# USB.net
KiCad netlist of a schematic drawn in EasyEDA Pro
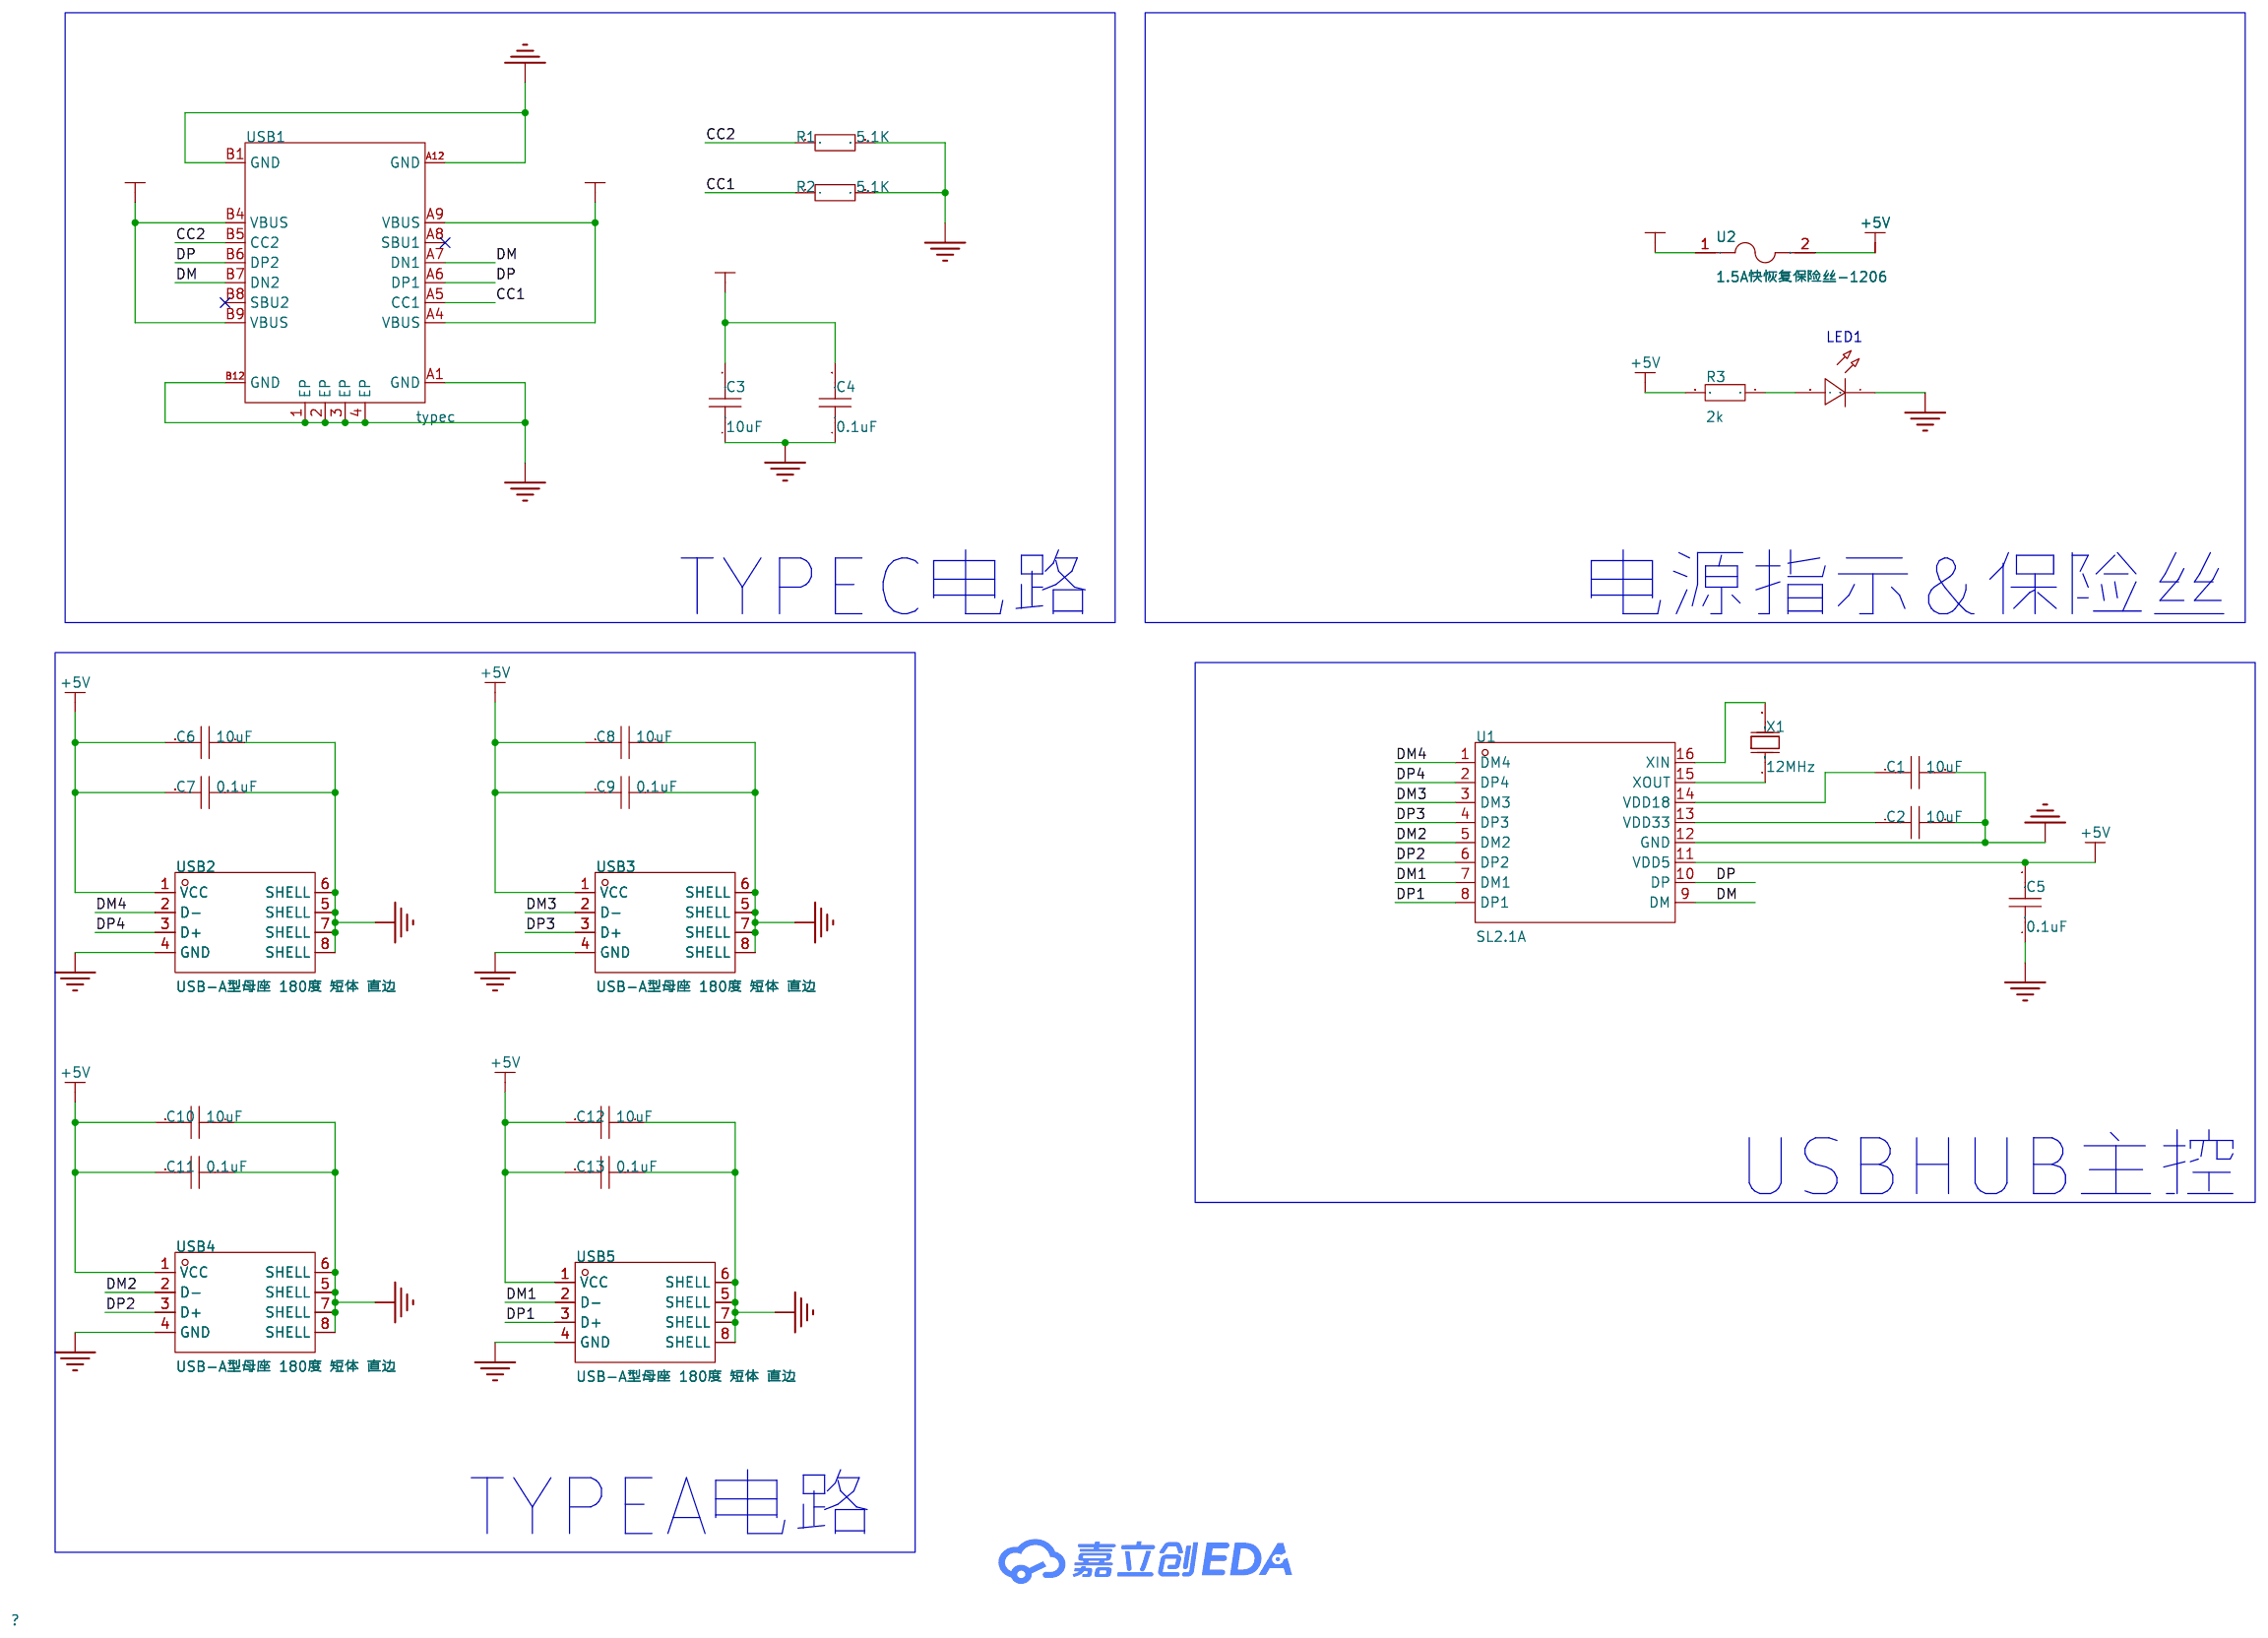
[diagram p0: schematic sheet]

(export (version "E")
  (design (tool "Eeschema 10.0.6"))
  (components
    (comp (ref "C1")
      (value "10uF")
      (footprint "easyedapro:C0805")
      (libsource (lib "easyedapro") (part "CapAcitance"))
    )
    (comp (ref "C2")
      (value "10uF")
      (footprint "easyedapro:C0805")
      (libsource (lib "easyedapro") (part "CapAcitance"))
    )
    (comp (ref "C3")
      (value "10uF")
      (footprint "easyedapro:C0805")
      (libsource (lib "easyedapro") (part "CapAcitance"))
    )
    (comp (ref "C4")
      (value "0.1uF")
      (footprint "easyedapro:C0805")
      (libsource (lib "easyedapro") (part "CapAcitance"))
    )
    (comp (ref "C5")
      (value "0.1uF")
      (footprint "easyedapro:C0805")
      (libsource (lib "easyedapro") (part "CapAcitance"))
    )
    (comp (ref "C6")
      (value "10uF")
      (footprint "easyedapro:C0805")
      (libsource (lib "easyedapro") (part "CapAcitance"))
    )
    (comp (ref "C7")
      (value "0.1uF")
      (footprint "easyedapro:C0805")
      (libsource (lib "easyedapro") (part "CapAcitance"))
    )
    (comp (ref "C8")
      (value "10uF")
      (footprint "easyedapro:C0805")
      (libsource (lib "easyedapro") (part "CapAcitance"))
    )
    (comp (ref "C9")
      (value "0.1uF")
      (footprint "easyedapro:C0805")
      (libsource (lib "easyedapro") (part "CapAcitance"))
    )
    (comp (ref "C10")
      (value "10uF")
      (footprint "easyedapro:C0805")
      (libsource (lib "easyedapro") (part "CapAcitance"))
    )
    (comp (ref "C11")
      (value "0.1uF")
      (footprint "easyedapro:C0805")
      (libsource (lib "easyedapro") (part "CapAcitance"))
    )
    (comp (ref "C12")
      (value "10uF")
      (footprint "easyedapro:C0805")
      (libsource (lib "easyedapro") (part "CapAcitance"))
    )
    (comp (ref "C13")
      (value "0.1uF")
      (footprint "easyedapro:C0805")
      (libsource (lib "easyedapro") (part "CapAcitance"))
    )
    (comp (ref "LED1")
      (value "~")
      (footprint "easyedapro:LED_0805")
      (libsource (lib "easyedapro") (part "LED_G"))
    )
    (comp (ref "R1") (value "5.1K") (footprint "easyedapro:R0805") (libsource (lib "easyedapro") (part "电阻")))
    (comp (ref "R2") (value "5.1K") (footprint "easyedapro:R0805") (libsource (lib "easyedapro") (part "电阻")))
    (comp (ref "R3") (value "2k") (footprint "easyedapro:R0805") (libsource (lib "easyedapro") (part "电阻")))
    (comp (ref "U1")
      (value "SL2.1A")
      (footprint "easyedapro:SOP-16_L10.0-W3.9-P1.27-LS6.0-BL")
      (description "SL2.1A是一颗高集成度,高性能,低功耗的USB2.0集线器主控芯片，支持USB2.0高速(480MHz),全速(12MHz)和低速模式(1.5MHz)，内置12MHz晶体振荡器。")
      (fields (field (name "Manufacturer") "CoreChips(和芯润德)"))
      (libsource (lib "easyedapro") (part "SL2.1A"))
    )
    (comp (ref "U2")
      (value "1.5A快恢复保险丝-1206")
      (footprint "easyedapro:F1206")
      (libsource (lib "easyedapro") (part "1.5A快恢复保险丝-1206"))
    )
    (comp (ref "USB1")
      (value "typec")
      (footprint "easyedapro:USB-C-SMD_KH-TYPE-C-16P")
      (libsource (lib "easyedapro") (part "TYPEC_C9900016956"))
    )
    (comp (ref "USB2")
      (value "USB-A型母座 180度 短体 直边")
      (footprint "easyedapro:USB-A-SMD_WT_C9900004571")
      (libsource (lib "easyedapro") (part "USB-A型母座 180度 短体 直边"))
    )
    (comp (ref "USB3")
      (value "USB-A型母座 180度 短体 直边")
      (footprint "easyedapro:USB-A-SMD_WT_C9900004571")
      (libsource (lib "easyedapro") (part "USB-A型母座 180度 短体 直边"))
    )
    (comp (ref "USB4")
      (value "USB-A型母座 180度 短体 直边")
      (footprint "easyedapro:USB-A-SMD_WT_C9900004571")
      (libsource (lib "easyedapro") (part "USB-A型母座 180度 短体 直边"))
    )
    (comp (ref "USB5")
      (value "USB-A型母座 180度 短体 直边")
      (footprint "easyedapro:USB-A-SMD_WT_C9900004571")
      (libsource (lib "easyedapro") (part "USB-A型母座 180度 短体 直边"))
    )
    (comp (ref "X1")
      (value "12MHz")
      (footprint "easyedapro:HC-49US_L11.0-W4.6-P4.88")
      (description "晶振类型:直插晶振;频率:12MHz;常温频差:±20ppm;外接负载电容:20pF;频率稳定度(全温):±30ppm;")
      (fields (field (name "Manufacturer Part") "49SAC12000202060") (field (name "Manufacturer") "JGHC(晶光华)"))
      (libsource (lib "easyedapro") (part "49SAC12000202060"))
    )
  )
  (nets
    (net (code "1") (name "+5V") (class "Default")
      (node (ref "C10") (pin "2") (pinfunction "2_2") (pintype "input"))
      (node (ref "C11") (pin "2") (pinfunction "2_2") (pintype "input"))
      (node (ref "C12") (pin "2") (pinfunction "2_2") (pintype "input"))
      (node (ref "C13") (pin "2") (pinfunction "2_2") (pintype "input"))
      (node (ref "C5") (pin "2") (pinfunction "2_2") (pintype "input"))
      (node (ref "C6") (pin "2") (pinfunction "2_2") (pintype "input"))
      (node (ref "C7") (pin "2") (pinfunction "2_2") (pintype "input"))
      (node (ref "C8") (pin "2") (pinfunction "2_2") (pintype "input"))
      (node (ref "C9") (pin "2") (pinfunction "2_2") (pintype "input"))
      (node (ref "R3") (pin "2") (pinfunction "2_2") (pintype "input"))
      (node (ref "U1") (pin "11") (pinfunction "VDD5_11") (pintype "unspecified"))
      (node (ref "U2") (pin "2") (pinfunction "2_2") (pintype "unspecified"))
      (node (ref "USB2") (pin "1") (pinfunction "VCC_1") (pintype "unspecified"))
      (node (ref "USB3") (pin "1") (pinfunction "VCC_1") (pintype "unspecified"))
      (node (ref "USB4") (pin "1") (pinfunction "VCC_1") (pintype "unspecified"))
      (node (ref "USB5") (pin "1") (pinfunction "VCC_1") (pintype "unspecified"))
    )
    (net (code "2") (name "/CC1") (class "Default")
      (node (ref "R2") (pin "1") (pinfunction "1_1") (pintype "input"))
      (node (ref "USB1") (pin "A5") (pinfunction "CC1_A5") (pintype "unspecified"))
    )
    (net (code "3") (name "/CC2") (class "Default")
      (node (ref "R1") (pin "1") (pinfunction "1_1") (pintype "input"))
      (node (ref "USB1") (pin "B5") (pinfunction "CC2_B5") (pintype "unspecified"))
    )
    (net (code "4") (name "/DM") (class "Default")
      (node (ref "U1") (pin "9") (pinfunction "DM_9") (pintype "unspecified"))
      (node (ref "USB1") (pin "A7") (pinfunction "DN1_A7") (pintype "unspecified"))
      (node (ref "USB1") (pin "B7") (pinfunction "DN2_B7") (pintype "unspecified"))
    )
    (net (code "5") (name "/DM1") (class "Default")
      (node (ref "U1") (pin "7") (pinfunction "DM1_7") (pintype "unspecified"))
      (node (ref "USB5") (pin "2") (pinfunction "D-_2") (pintype "unspecified"))
    )
    (net (code "6") (name "/DM2") (class "Default")
      (node (ref "U1") (pin "5") (pinfunction "DM2_5") (pintype "unspecified"))
      (node (ref "USB4") (pin "2") (pinfunction "D-_2") (pintype "unspecified"))
    )
    (net (code "7") (name "/DM3") (class "Default")
      (node (ref "U1") (pin "3") (pinfunction "DM3_3") (pintype "unspecified"))
      (node (ref "USB3") (pin "2") (pinfunction "D-_2") (pintype "unspecified"))
    )
    (net (code "8") (name "/DM4") (class "Default")
      (node (ref "U1") (pin "1") (pinfunction "DM4_1") (pintype "unspecified"))
      (node (ref "USB2") (pin "2") (pinfunction "D-_2") (pintype "unspecified"))
    )
    (net (code "9") (name "/DP") (class "Default")
      (node (ref "U1") (pin "10") (pinfunction "DP_10") (pintype "unspecified"))
      (node (ref "USB1") (pin "A6") (pinfunction "DP1_A6") (pintype "unspecified"))
      (node (ref "USB1") (pin "B6") (pinfunction "DP2_B6") (pintype "unspecified"))
    )
    (net (code "10") (name "/DP1") (class "Default")
      (node (ref "U1") (pin "8") (pinfunction "DP1_8") (pintype "unspecified"))
      (node (ref "USB5") (pin "3") (pinfunction "D+_3") (pintype "unspecified"))
    )
    (net (code "11") (name "/DP2") (class "Default")
      (node (ref "U1") (pin "6") (pinfunction "DP2_6") (pintype "unspecified"))
      (node (ref "USB4") (pin "3") (pinfunction "D+_3") (pintype "unspecified"))
    )
    (net (code "12") (name "/DP3") (class "Default")
      (node (ref "U1") (pin "4") (pinfunction "DP3_4") (pintype "unspecified"))
      (node (ref "USB3") (pin "3") (pinfunction "D+_3") (pintype "unspecified"))
    )
    (net (code "13") (name "/DP4") (class "Default")
      (node (ref "U1") (pin "2") (pinfunction "DP4_2") (pintype "unspecified"))
      (node (ref "USB2") (pin "3") (pinfunction "D+_3") (pintype "unspecified"))
    )
    (net (code "14") (name "GND") (class "Default")
      (node (ref "C1") (pin "2") (pinfunction "2_2") (pintype "input"))
      (node (ref "C10") (pin "1") (pinfunction "1_1") (pintype "input"))
      (node (ref "C11") (pin "1") (pinfunction "1_1") (pintype "input"))
      (node (ref "C12") (pin "1") (pinfunction "1_1") (pintype "input"))
      (node (ref "C13") (pin "1") (pinfunction "1_1") (pintype "input"))
      (node (ref "C2") (pin "2") (pinfunction "2_2") (pintype "input"))
      (node (ref "C3") (pin "1") (pinfunction "1_1") (pintype "input"))
      (node (ref "C4") (pin "1") (pinfunction "1_1") (pintype "input"))
      (node (ref "C5") (pin "1") (pinfunction "1_1") (pintype "input"))
      (node (ref "C6") (pin "1") (pinfunction "1_1") (pintype "input"))
      (node (ref "C7") (pin "1") (pinfunction "1_1") (pintype "input"))
      (node (ref "C8") (pin "1") (pinfunction "1_1") (pintype "input"))
      (node (ref "C9") (pin "1") (pinfunction "1_1") (pintype "input"))
      (node (ref "LED1") (pin "1") (pinfunction "C_1") (pintype "input"))
      (node (ref "R1") (pin "2") (pinfunction "2_2") (pintype "input"))
      (node (ref "R2") (pin "2") (pinfunction "2_2") (pintype "input"))
      (node (ref "U1") (pin "12") (pinfunction "GND_12") (pintype "unspecified"))
      (node (ref "USB1") (pin "1") (pinfunction "EP_1") (pintype "unspecified"))
      (node (ref "USB1") (pin "2") (pinfunction "EP_2") (pintype "unspecified"))
      (node (ref "USB1") (pin "3") (pinfunction "EP_3") (pintype "unspecified"))
      (node (ref "USB1") (pin "4") (pinfunction "EP_4") (pintype "unspecified"))
      (node (ref "USB1") (pin "A1") (pinfunction "GND_A1") (pintype "unspecified"))
      (node (ref "USB1") (pin "A12") (pinfunction "GND_A12") (pintype "unspecified"))
      (node (ref "USB1") (pin "B1") (pinfunction "GND_B1") (pintype "unspecified"))
      (node (ref "USB1") (pin "B12") (pinfunction "GND_B12") (pintype "unspecified"))
      (node (ref "USB2") (pin "4") (pinfunction "GND_4") (pintype "unspecified"))
      (node (ref "USB2") (pin "5") (pinfunction "SHELL_5") (pintype "unspecified"))
      (node (ref "USB2") (pin "6") (pinfunction "SHELL_6") (pintype "unspecified"))
      (node (ref "USB2") (pin "7") (pinfunction "SHELL_7") (pintype "unspecified"))
      (node (ref "USB2") (pin "8") (pinfunction "SHELL_8") (pintype "unspecified"))
      (node (ref "USB3") (pin "4") (pinfunction "GND_4") (pintype "unspecified"))
      (node (ref "USB3") (pin "5") (pinfunction "SHELL_5") (pintype "unspecified"))
      (node (ref "USB3") (pin "6") (pinfunction "SHELL_6") (pintype "unspecified"))
      (node (ref "USB3") (pin "7") (pinfunction "SHELL_7") (pintype "unspecified"))
      (node (ref "USB3") (pin "8") (pinfunction "SHELL_8") (pintype "unspecified"))
      (node (ref "USB4") (pin "4") (pinfunction "GND_4") (pintype "unspecified"))
      (node (ref "USB4") (pin "5") (pinfunction "SHELL_5") (pintype "unspecified"))
      (node (ref "USB4") (pin "6") (pinfunction "SHELL_6") (pintype "unspecified"))
      (node (ref "USB4") (pin "7") (pinfunction "SHELL_7") (pintype "unspecified"))
      (node (ref "USB4") (pin "8") (pinfunction "SHELL_8") (pintype "unspecified"))
      (node (ref "USB5") (pin "4") (pinfunction "GND_4") (pintype "unspecified"))
      (node (ref "USB5") (pin "5") (pinfunction "SHELL_5") (pintype "unspecified"))
      (node (ref "USB5") (pin "6") (pinfunction "SHELL_6") (pintype "unspecified"))
      (node (ref "USB5") (pin "7") (pinfunction "SHELL_7") (pintype "unspecified"))
      (node (ref "USB5") (pin "8") (pinfunction "SHELL_8") (pintype "unspecified"))
    )
    (net (code "15") (name "Net-(LED1-A)") (class "Default")
      (node (ref "LED1") (pin "2") (pinfunction "A_2") (pintype "input"))
      (node (ref "R3") (pin "1") (pinfunction "1_1") (pintype "input"))
    )
    (net (code "16") (name "Net-(U1-VDD18)") (class "Default")
      (node (ref "C1") (pin "1") (pinfunction "1_1") (pintype "input"))
      (node (ref "U1") (pin "14") (pinfunction "VDD18_14") (pintype "unspecified"))
    )
    (net (code "17") (name "Net-(U1-VDD33)") (class "Default")
      (node (ref "C2") (pin "1") (pinfunction "1_1") (pintype "input"))
      (node (ref "U1") (pin "13") (pinfunction "VDD33_13") (pintype "unspecified"))
    )
    (net (code "18") (name "Net-(U1-XIN)") (class "Default")
      (node (ref "U1") (pin "16") (pinfunction "XIN_16") (pintype "unspecified"))
      (node (ref "X1") (pin "2") (pinfunction "OSC2_2") (pintype "input"))
    )
    (net (code "19") (name "Net-(U1-XOUT)") (class "Default")
      (node (ref "U1") (pin "15") (pinfunction "XOUT_15") (pintype "unspecified"))
      (node (ref "X1") (pin "1") (pinfunction "OSC1_1") (pintype "input"))
    )
    (net (code "20") (name "VCC+5V") (class "Default")
      (node (ref "C3") (pin "2") (pinfunction "2_2") (pintype "input"))
      (node (ref "C4") (pin "2") (pinfunction "2_2") (pintype "input"))
      (node (ref "U2") (pin "1") (pinfunction "1_1") (pintype "unspecified"))
      (node (ref "USB1") (pin "A4") (pinfunction "VBUS_A4") (pintype "unspecified"))
      (node (ref "USB1") (pin "A9") (pinfunction "VBUS_A9") (pintype "unspecified"))
      (node (ref "USB1") (pin "B4") (pinfunction "VBUS_B4") (pintype "unspecified"))
      (node (ref "USB1") (pin "B9") (pinfunction "VBUS_B9") (pintype "unspecified"))
    )
    (net (code "21") (name "unconnected-(USB1-SBU1-PadA8)") (class "Default")
      (node (ref "USB1") (pin "A8") (pinfunction "SBU1_A8") (pintype "unspecified+no_connect"))
    )
    (net (code "22") (name "unconnected-(USB1-SBU2-PadB8)") (class "Default")
      (node (ref "USB1") (pin "B8") (pinfunction "SBU2_B8") (pintype "unspecified+no_connect"))
    )
  )
)
